# DM3390_Connector_A.net
KiCad netlist of a schematic drawn in Altium Designer
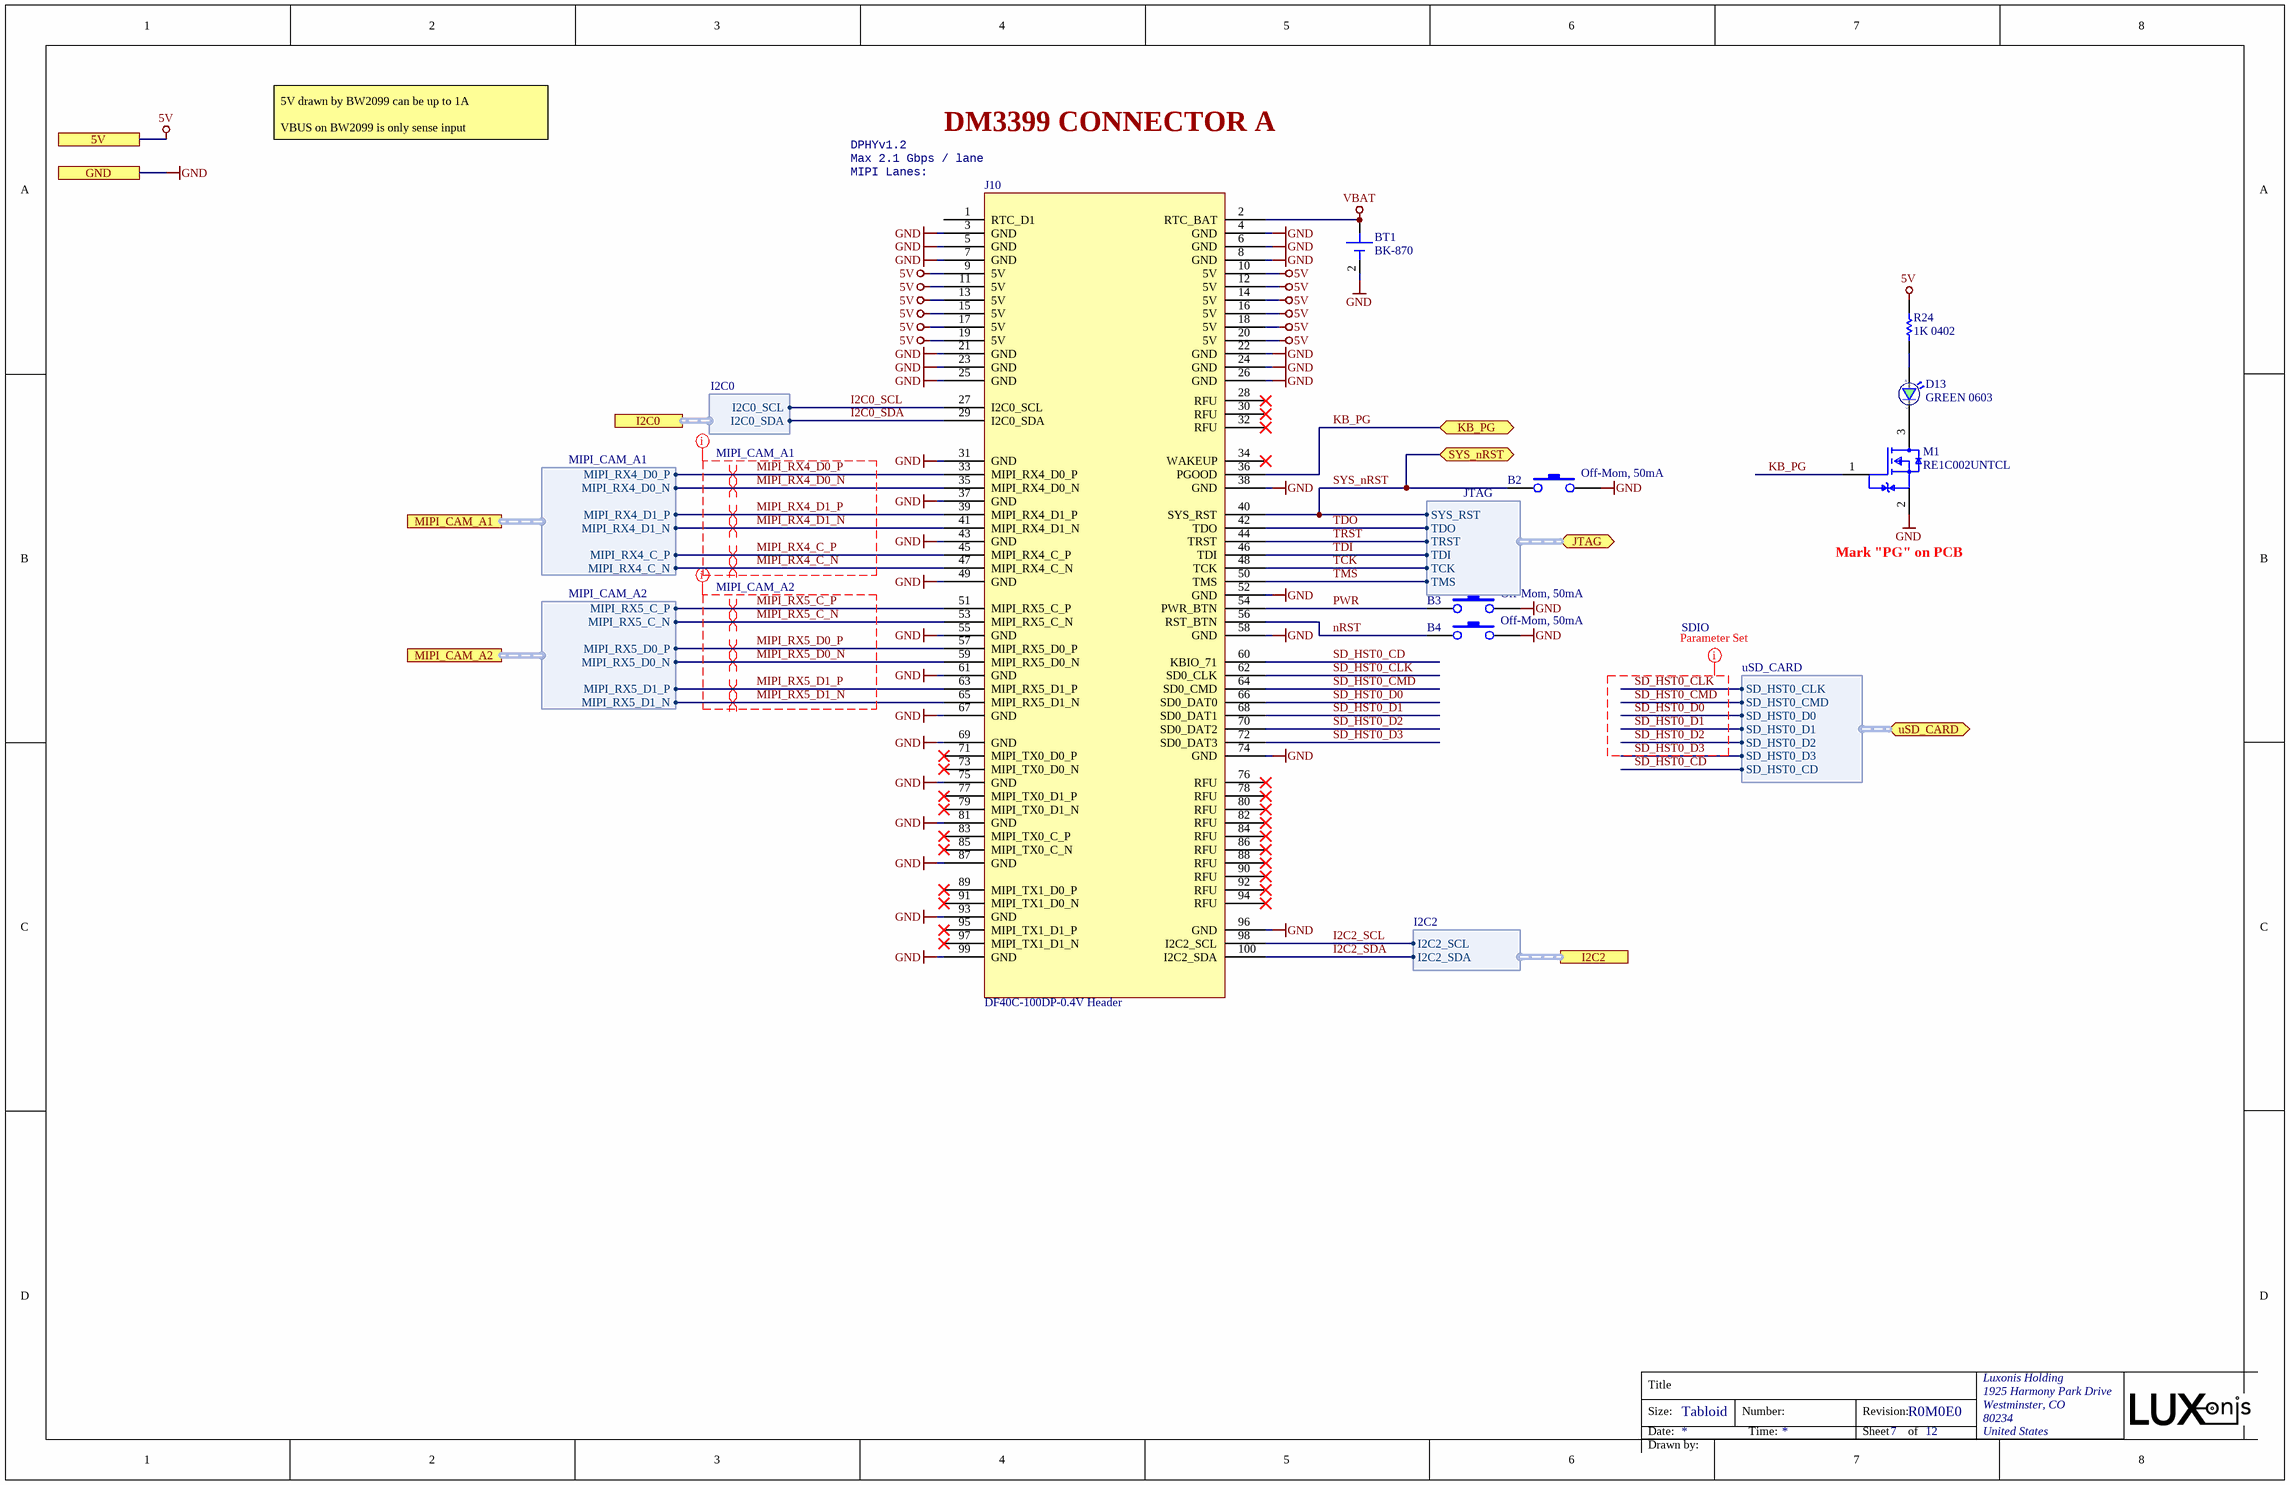
[diagram p0: DM3390_Connector_A.SchDoc]

(export (version "E")
  (design (tool "Eeschema 10.0.6"))
  (components
    (comp (ref "B2")
      (value "Off-Mom, 50mA")
      (footprint "LuxonisMaster:DTSM-32N-V")
      (description "SWITCH TACTILE SMT 3.5mm * 6mm , brown 160gf")
      (libsource (lib "LuxonisMaster") (part "DTSM-32N-V"))
    )
    (comp (ref "B3")
      (value "Off-Mom, 50mA")
      (footprint "LuxonisMaster:DTSM-32N-V")
      (description "SWITCH TACTILE SMT 3.5mm * 6mm , brown 160gf")
      (libsource (lib "LuxonisMaster") (part "DTSM-32N-V"))
    )
    (comp (ref "B4")
      (value "Off-Mom, 50mA")
      (footprint "LuxonisMaster:DTSM-32N-V")
      (description "SWITCH TACTILE SMT 3.5mm * 6mm , brown 160gf")
      (libsource (lib "LuxonisMaster") (part "DTSM-32N-V"))
    )
    (comp (ref "BT1")
      (value "BK-870")
      (footprint "MPD_BK-870")
      (description "Battery Retainer Coin 10MM SMD")
      (libsource (lib "LuxonisMaster") (part "BK-870"))
    )
    (comp (ref "D13")
      (value "GREEN 0603")
      (footprint "LuxonisMaster:SML_D1xx8W")
      (description "LED GREEN DIFFUSED 0603 SMD Green 572nm LED Indication - Discrete 2.2V 0603 (1608 Metric)")
      (fields (field (name "MANUFACTURER") "Rohm") (field (name "MANUFACTURER PART NUMBER") "SML-D12M8WT86"))
      (libsource (lib "LuxonisMaster") (part "SML-D12M8WT86"))
    )
    (comp (ref "J10")
      (value "DF40C-100DP-0.4V Header")
      (footprint "LuxonisMaster:CON_A_SoM-MAX_DF40HC-3.0-100DS-0.4V_minpad")
      (description "CONN HDR 100POS 0.4MM SMD GOLD BW2099 SYMBOL")
      (fields (field (name "MFG") "Hirose"))
      (libsource (lib "LuxonisMaster") (part "DF40HC(3.0)-100DS-0.4V_OAK-SoM-MAX_A"))
    )
    (comp (ref "M1")
      (value "RE1C002UNTCL")
      (footprint "LuxonisMaster:RE1C002UNTCL")
      (description "MOSFET N-CH 20V 0.2A EMT3")
      (libsource (lib "LuxonisMaster") (part "RE1C002UNTCL"))
    )
    (comp (ref "R24")
      (value "1K 0402")
      (footprint "RES_Altium_Vault_Generic:RESC0402(1005)_N")
      (fields (field (name "TOLERANCE") "1%"))
      (libsource (lib "LuxonisMaster") (part "RC0402FR-071KL"))
    )
  )
  (nets
    (net (code "7") (name "/I2C0_SCL") (class "Default")
      (node (ref "J10") (pin "27") (pinfunction "I2C0_SCL_27") (pintype "passive"))
    )
    (net (code "8") (name "/I2C0_SDA") (class "Default")
      (node (ref "J10") (pin "29") (pinfunction "I2C0_SDA_29") (pintype "passive"))
    )
    (net (code "9") (name "/I2C2_SCL") (class "Default")
      (node (ref "J10") (pin "98") (pinfunction "I2C2_SCL_98") (pintype "passive"))
    )
    (net (code "10") (name "/I2C2_SDA") (class "Default")
      (node (ref "J10") (pin "100") (pinfunction "I2C2_SDA_100") (pintype "passive"))
    )
    (net (code "11") (name "/KB_PG") (class "Default")
      (node (ref "J10") (pin "36") (pinfunction "PGOOD_36") (pintype "passive"))
      (node (ref "M1") (pin "1") (pinfunction "Gate_1") (pintype "passive"))
    )
    (net (code "12") (name "/MIPI_RX4_C_N") (class "Default")
      (node (ref "J10") (pin "47") (pinfunction "MIPI_RX4_C_N_47") (pintype "passive"))
    )
    (net (code "13") (name "/MIPI_RX4_C_P") (class "Default")
      (node (ref "J10") (pin "45") (pinfunction "MIPI_RX4_C_P_45") (pintype "passive"))
    )
    (net (code "14") (name "/MIPI_RX4_D0_N") (class "Default")
      (node (ref "J10") (pin "35") (pinfunction "MIPI_RX4_D0_N_35") (pintype "passive"))
    )
    (net (code "15") (name "/MIPI_RX4_D0_P") (class "Default")
      (node (ref "J10") (pin "33") (pinfunction "MIPI_RX4_D0_P_33") (pintype "passive"))
    )
    (net (code "16") (name "/MIPI_RX4_D1_N") (class "Default")
      (node (ref "J10") (pin "41") (pinfunction "MIPI_RX4_D1_N_41") (pintype "passive"))
    )
    (net (code "17") (name "/MIPI_RX4_D1_P") (class "Default")
      (node (ref "J10") (pin "39") (pinfunction "MIPI_RX4_D1_P_39") (pintype "passive"))
    )
    (net (code "18") (name "/MIPI_RX5_C_N") (class "Default")
      (node (ref "J10") (pin "53") (pinfunction "MIPI_RX5_C_N_53") (pintype "passive"))
    )
    (net (code "19") (name "/MIPI_RX5_C_P") (class "Default")
      (node (ref "J10") (pin "51") (pinfunction "MIPI_RX5_C_P_51") (pintype "passive"))
    )
    (net (code "20") (name "/MIPI_RX5_D0_N") (class "Default")
      (node (ref "J10") (pin "59") (pinfunction "MIPI_RX5_D0_N_59") (pintype "passive"))
    )
    (net (code "21") (name "/MIPI_RX5_D0_P") (class "Default")
      (node (ref "J10") (pin "57") (pinfunction "MIPI_RX5_D0_P_57") (pintype "passive"))
    )
    (net (code "22") (name "/MIPI_RX5_D1_N") (class "Default")
      (node (ref "J10") (pin "65") (pinfunction "MIPI_RX5_D1_N_65") (pintype "passive"))
    )
    (net (code "23") (name "/MIPI_RX5_D1_P") (class "Default")
      (node (ref "J10") (pin "63") (pinfunction "MIPI_RX5_D1_P_63") (pintype "passive"))
    )
    (net (code "24") (name "/PWR") (class "Default")
      (node (ref "B3") (pin "2") (pinfunction "2_2") (pintype "passive"))
      (node (ref "J10") (pin "54") (pinfunction "PWR_BTN_54") (pintype "passive"))
    )
    (net (code "25") (name "/SD_HST0_CD") (class "Default")
      (node (ref "J10") (pin "60") (pinfunction "KBIO_71_60") (pintype "passive"))
    )
    (net (code "26") (name "/SD_HST0_CLK") (class "Default")
      (node (ref "J10") (pin "62") (pinfunction "SD0_CLK_62") (pintype "passive"))
    )
    (net (code "27") (name "/SD_HST0_CMD") (class "Default")
      (node (ref "J10") (pin "64") (pinfunction "SD0_CMD_64") (pintype "passive"))
    )
    (net (code "28") (name "/SD_HST0_D0") (class "Default")
      (node (ref "J10") (pin "66") (pinfunction "SD0_DAT0_66") (pintype "passive"))
    )
    (net (code "29") (name "/SD_HST0_D1") (class "Default")
      (node (ref "J10") (pin "68") (pinfunction "SD0_DAT1_68") (pintype "passive"))
    )
    (net (code "30") (name "/SD_HST0_D2") (class "Default")
      (node (ref "J10") (pin "70") (pinfunction "SD0_DAT2_70") (pintype "passive"))
    )
    (net (code "31") (name "/SD_HST0_D3") (class "Default")
      (node (ref "J10") (pin "72") (pinfunction "SD0_DAT3_72") (pintype "passive"))
    )
    (net (code "32") (name "/SYS_nRST") (class "Default")
      (node (ref "B2") (pin "2") (pinfunction "2_2") (pintype "passive"))
      (node (ref "J10") (pin "40") (pinfunction "SYS_RST_40") (pintype "passive"))
    )
    (net (code "33") (name "/TCK") (class "Default")
      (node (ref "J10") (pin "48") (pinfunction "TCK_48") (pintype "passive"))
    )
    (net (code "34") (name "/TDI") (class "Default")
      (node (ref "J10") (pin "46") (pinfunction "TDI_46") (pintype "passive"))
    )
    (net (code "35") (name "/TDO") (class "Default")
      (node (ref "J10") (pin "42") (pinfunction "TDO_42") (pintype "passive"))
    )
    (net (code "36") (name "/TMS") (class "Default")
      (node (ref "J10") (pin "50") (pinfunction "TMS_50") (pintype "passive"))
    )
    (net (code "37") (name "/TRST") (class "Default")
      (node (ref "J10") (pin "44") (pinfunction "TRST_44") (pintype "passive"))
    )
    (net (code "38") (name "/nRST") (class "Default")
      (node (ref "B4") (pin "2") (pinfunction "2_2") (pintype "passive"))
      (node (ref "J10") (pin "56") (pinfunction "RST_BTN_56") (pintype "passive"))
    )
    (net (code "45") (name "5V") (class "Default")
      (node (ref "J10") (pin "10") (pinfunction "5V_10") (pintype "passive"))
      (node (ref "J10") (pin "11") (pinfunction "5V_11") (pintype "passive"))
      (node (ref "J10") (pin "12") (pinfunction "5V_12") (pintype "passive"))
      (node (ref "J10") (pin "13") (pinfunction "5V_13") (pintype "passive"))
      (node (ref "J10") (pin "14") (pinfunction "5V_14") (pintype "passive"))
      (node (ref "J10") (pin "15") (pinfunction "5V_15") (pintype "passive"))
      (node (ref "J10") (pin "16") (pinfunction "5V_16") (pintype "passive"))
      (node (ref "J10") (pin "17") (pinfunction "5V_17") (pintype "passive"))
      (node (ref "J10") (pin "18") (pinfunction "5V_18") (pintype "passive"))
      (node (ref "J10") (pin "19") (pinfunction "5V_19") (pintype "passive"))
      (node (ref "J10") (pin "20") (pinfunction "5V_20") (pintype "passive"))
      (node (ref "J10") (pin "9") (pinfunction "5V_9") (pintype "passive"))
      (node (ref "R24") (pin "2") (pinfunction "2_2") (pintype "passive"))
    )
    (net (code "46") (name "GND") (class "Default")
      (node (ref "B2") (pin "1") (pinfunction "1_1") (pintype "passive"))
      (node (ref "B3") (pin "1") (pinfunction "1_1") (pintype "passive"))
      (node (ref "B4") (pin "1") (pinfunction "1_1") (pintype "passive"))
      (node (ref "BT1") (pin "2") (pinfunction "M_2") (pintype "passive"))
      (node (ref "J10") (pin "21") (pinfunction "GND_21") (pintype "passive"))
      (node (ref "J10") (pin "22") (pinfunction "GND_22") (pintype "passive"))
      (node (ref "J10") (pin "23") (pinfunction "GND_23") (pintype "passive"))
      (node (ref "J10") (pin "24") (pinfunction "GND_24") (pintype "passive"))
      (node (ref "J10") (pin "25") (pinfunction "GND_25") (pintype "passive"))
      (node (ref "J10") (pin "26") (pinfunction "GND_26") (pintype "passive"))
      (node (ref "J10") (pin "3") (pinfunction "GND_3") (pintype "passive"))
      (node (ref "J10") (pin "31") (pinfunction "GND_31") (pintype "passive"))
      (node (ref "J10") (pin "37") (pinfunction "GND_37") (pintype "passive"))
      (node (ref "J10") (pin "38") (pinfunction "GND_38") (pintype "passive"))
      (node (ref "J10") (pin "4") (pinfunction "GND_4") (pintype "passive"))
      (node (ref "J10") (pin "43") (pinfunction "GND_43") (pintype "passive"))
      (node (ref "J10") (pin "49") (pinfunction "GND_49") (pintype "passive"))
      (node (ref "J10") (pin "5") (pinfunction "GND_5") (pintype "passive"))
      (node (ref "J10") (pin "52") (pinfunction "GND_52") (pintype "passive"))
      (node (ref "J10") (pin "55") (pinfunction "GND_55") (pintype "passive"))
      (node (ref "J10") (pin "58") (pinfunction "GND_58") (pintype "passive"))
      (node (ref "J10") (pin "6") (pinfunction "GND_6") (pintype "passive"))
      (node (ref "J10") (pin "61") (pinfunction "GND_61") (pintype "passive"))
      (node (ref "J10") (pin "67") (pinfunction "GND_67") (pintype "passive"))
      (node (ref "J10") (pin "69") (pinfunction "GND_69") (pintype "passive"))
      (node (ref "J10") (pin "7") (pinfunction "GND_7") (pintype "passive"))
      (node (ref "J10") (pin "74") (pinfunction "GND_74") (pintype "passive"))
      (node (ref "J10") (pin "75") (pinfunction "GND_75") (pintype "passive"))
      (node (ref "J10") (pin "8") (pinfunction "GND_8") (pintype "passive"))
      (node (ref "J10") (pin "81") (pinfunction "GND_81") (pintype "passive"))
      (node (ref "J10") (pin "87") (pinfunction "GND_87") (pintype "passive"))
      (node (ref "J10") (pin "93") (pinfunction "GND_93") (pintype "passive"))
      (node (ref "J10") (pin "96") (pinfunction "GND_96") (pintype "passive"))
      (node (ref "J10") (pin "99") (pinfunction "GND_99") (pintype "passive"))
      (node (ref "M1") (pin "2") (pinfunction "Source_2") (pintype "passive"))
    )
    (net (code "47") (name "Net-(D13-A)") (class "Default")
      (node (ref "D13") (pin "2") (pinfunction "A_2") (pintype "passive"))
      (node (ref "R24") (pin "1") (pinfunction "1_1") (pintype "passive"))
    )
    (net (code "48") (name "Net-(D13-C)") (class "Default")
      (node (ref "D13") (pin "1") (pinfunction "C_1") (pintype "passive"))
      (node (ref "M1") (pin "3") (pinfunction "Drain_3") (pintype "passive"))
    )
    (net (code "49") (name "VBAT") (class "Default")
      (node (ref "BT1") (pin "1") (pinfunction "P_1") (pintype "passive"))
      (node (ref "BT1") (pin "3") (pinfunction "P_3") (pintype "passive"))
      (node (ref "J10") (pin "2") (pinfunction "RTC_BAT_2") (pintype "passive"))
    )
    (net (code "50") (name "unconnected-(J10-MIPI_TX0_C_N-Pad85)") (class "Default")
      (node (ref "J10") (pin "85") (pinfunction "MIPI_TX0_C_N_85") (pintype "passive+no_connect"))
    )
    (net (code "51") (name "unconnected-(J10-MIPI_TX0_C_P-Pad83)") (class "Default")
      (node (ref "J10") (pin "83") (pinfunction "MIPI_TX0_C_P_83") (pintype "passive+no_connect"))
    )
    (net (code "52") (name "unconnected-(J10-MIPI_TX0_D0_N-Pad73)") (class "Default")
      (node (ref "J10") (pin "73") (pinfunction "MIPI_TX0_D0_N_73") (pintype "passive+no_connect"))
    )
    (net (code "53") (name "unconnected-(J10-MIPI_TX0_D0_P-Pad71)") (class "Default")
      (node (ref "J10") (pin "71") (pinfunction "MIPI_TX0_D0_P_71") (pintype "passive+no_connect"))
    )
    (net (code "54") (name "unconnected-(J10-MIPI_TX0_D1_N-Pad79)") (class "Default")
      (node (ref "J10") (pin "79") (pinfunction "MIPI_TX0_D1_N_79") (pintype "passive+no_connect"))
    )
    (net (code "55") (name "unconnected-(J10-MIPI_TX0_D1_P-Pad77)") (class "Default")
      (node (ref "J10") (pin "77") (pinfunction "MIPI_TX0_D1_P_77") (pintype "passive+no_connect"))
    )
    (net (code "56") (name "unconnected-(J10-MIPI_TX1_D0_N-Pad91)") (class "Default")
      (node (ref "J10") (pin "91") (pinfunction "MIPI_TX1_D0_N_91") (pintype "passive+no_connect"))
    )
    (net (code "57") (name "unconnected-(J10-MIPI_TX1_D0_P-Pad89)") (class "Default")
      (node (ref "J10") (pin "89") (pinfunction "MIPI_TX1_D0_P_89") (pintype "passive+no_connect"))
    )
    (net (code "58") (name "unconnected-(J10-MIPI_TX1_D1_N-Pad97)") (class "Default")
      (node (ref "J10") (pin "97") (pinfunction "MIPI_TX1_D1_N_97") (pintype "passive+no_connect"))
    )
    (net (code "59") (name "unconnected-(J10-MIPI_TX1_D1_P-Pad95)") (class "Default")
      (node (ref "J10") (pin "95") (pinfunction "MIPI_TX1_D1_P_95") (pintype "passive+no_connect"))
    )
    (net (code "60") (name "unconnected-(J10-RFU-Pad28)") (class "Default")
      (node (ref "J10") (pin "28") (pinfunction "RFU_28") (pintype "passive+no_connect"))
    )
    (net (code "61") (name "unconnected-(J10-RFU-Pad30)") (class "Default")
      (node (ref "J10") (pin "30") (pinfunction "RFU_30") (pintype "passive+no_connect"))
    )
    (net (code "62") (name "unconnected-(J10-RFU-Pad32)") (class "Default")
      (node (ref "J10") (pin "32") (pinfunction "RFU_32") (pintype "passive+no_connect"))
    )
    (net (code "63") (name "unconnected-(J10-RFU-Pad76)") (class "Default")
      (node (ref "J10") (pin "76") (pinfunction "RFU_76") (pintype "passive+no_connect"))
    )
    (net (code "64") (name "unconnected-(J10-RFU-Pad78)") (class "Default")
      (node (ref "J10") (pin "78") (pinfunction "RFU_78") (pintype "passive+no_connect"))
    )
    (net (code "65") (name "unconnected-(J10-RFU-Pad80)") (class "Default")
      (node (ref "J10") (pin "80") (pinfunction "RFU_80") (pintype "passive+no_connect"))
    )
    (net (code "66") (name "unconnected-(J10-RFU-Pad82)") (class "Default")
      (node (ref "J10") (pin "82") (pinfunction "RFU_82") (pintype "passive+no_connect"))
    )
    (net (code "67") (name "unconnected-(J10-RFU-Pad84)") (class "Default")
      (node (ref "J10") (pin "84") (pinfunction "RFU_84") (pintype "passive+no_connect"))
    )
    (net (code "68") (name "unconnected-(J10-RFU-Pad86)") (class "Default")
      (node (ref "J10") (pin "86") (pinfunction "RFU_86") (pintype "passive+no_connect"))
    )
    (net (code "69") (name "unconnected-(J10-RFU-Pad88)") (class "Default")
      (node (ref "J10") (pin "88") (pinfunction "RFU_88") (pintype "passive+no_connect"))
    )
    (net (code "70") (name "unconnected-(J10-RFU-Pad90)") (class "Default")
      (node (ref "J10") (pin "90") (pinfunction "RFU_90") (pintype "passive+no_connect"))
    )
    (net (code "71") (name "unconnected-(J10-RFU-Pad92)") (class "Default")
      (node (ref "J10") (pin "92") (pinfunction "RFU_92") (pintype "passive+no_connect"))
    )
    (net (code "72") (name "unconnected-(J10-RFU-Pad94)") (class "Default")
      (node (ref "J10") (pin "94") (pinfunction "RFU_94") (pintype "passive+no_connect"))
    )
    (net (code "73") (name "unconnected-(J10-RTC_D1-Pad1)") (class "Default")
      (node (ref "J10") (pin "1") (pinfunction "RTC_D1_1") (pintype "passive"))
    )
    (net (code "74") (name "unconnected-(J10-WAKEUP-Pad34)") (class "Default")
      (node (ref "J10") (pin "34") (pinfunction "WAKEUP_34") (pintype "passive+no_connect"))
    )
  )
)
